# PCB.net
KiCad netlist of a schematic drawn in EAGLE
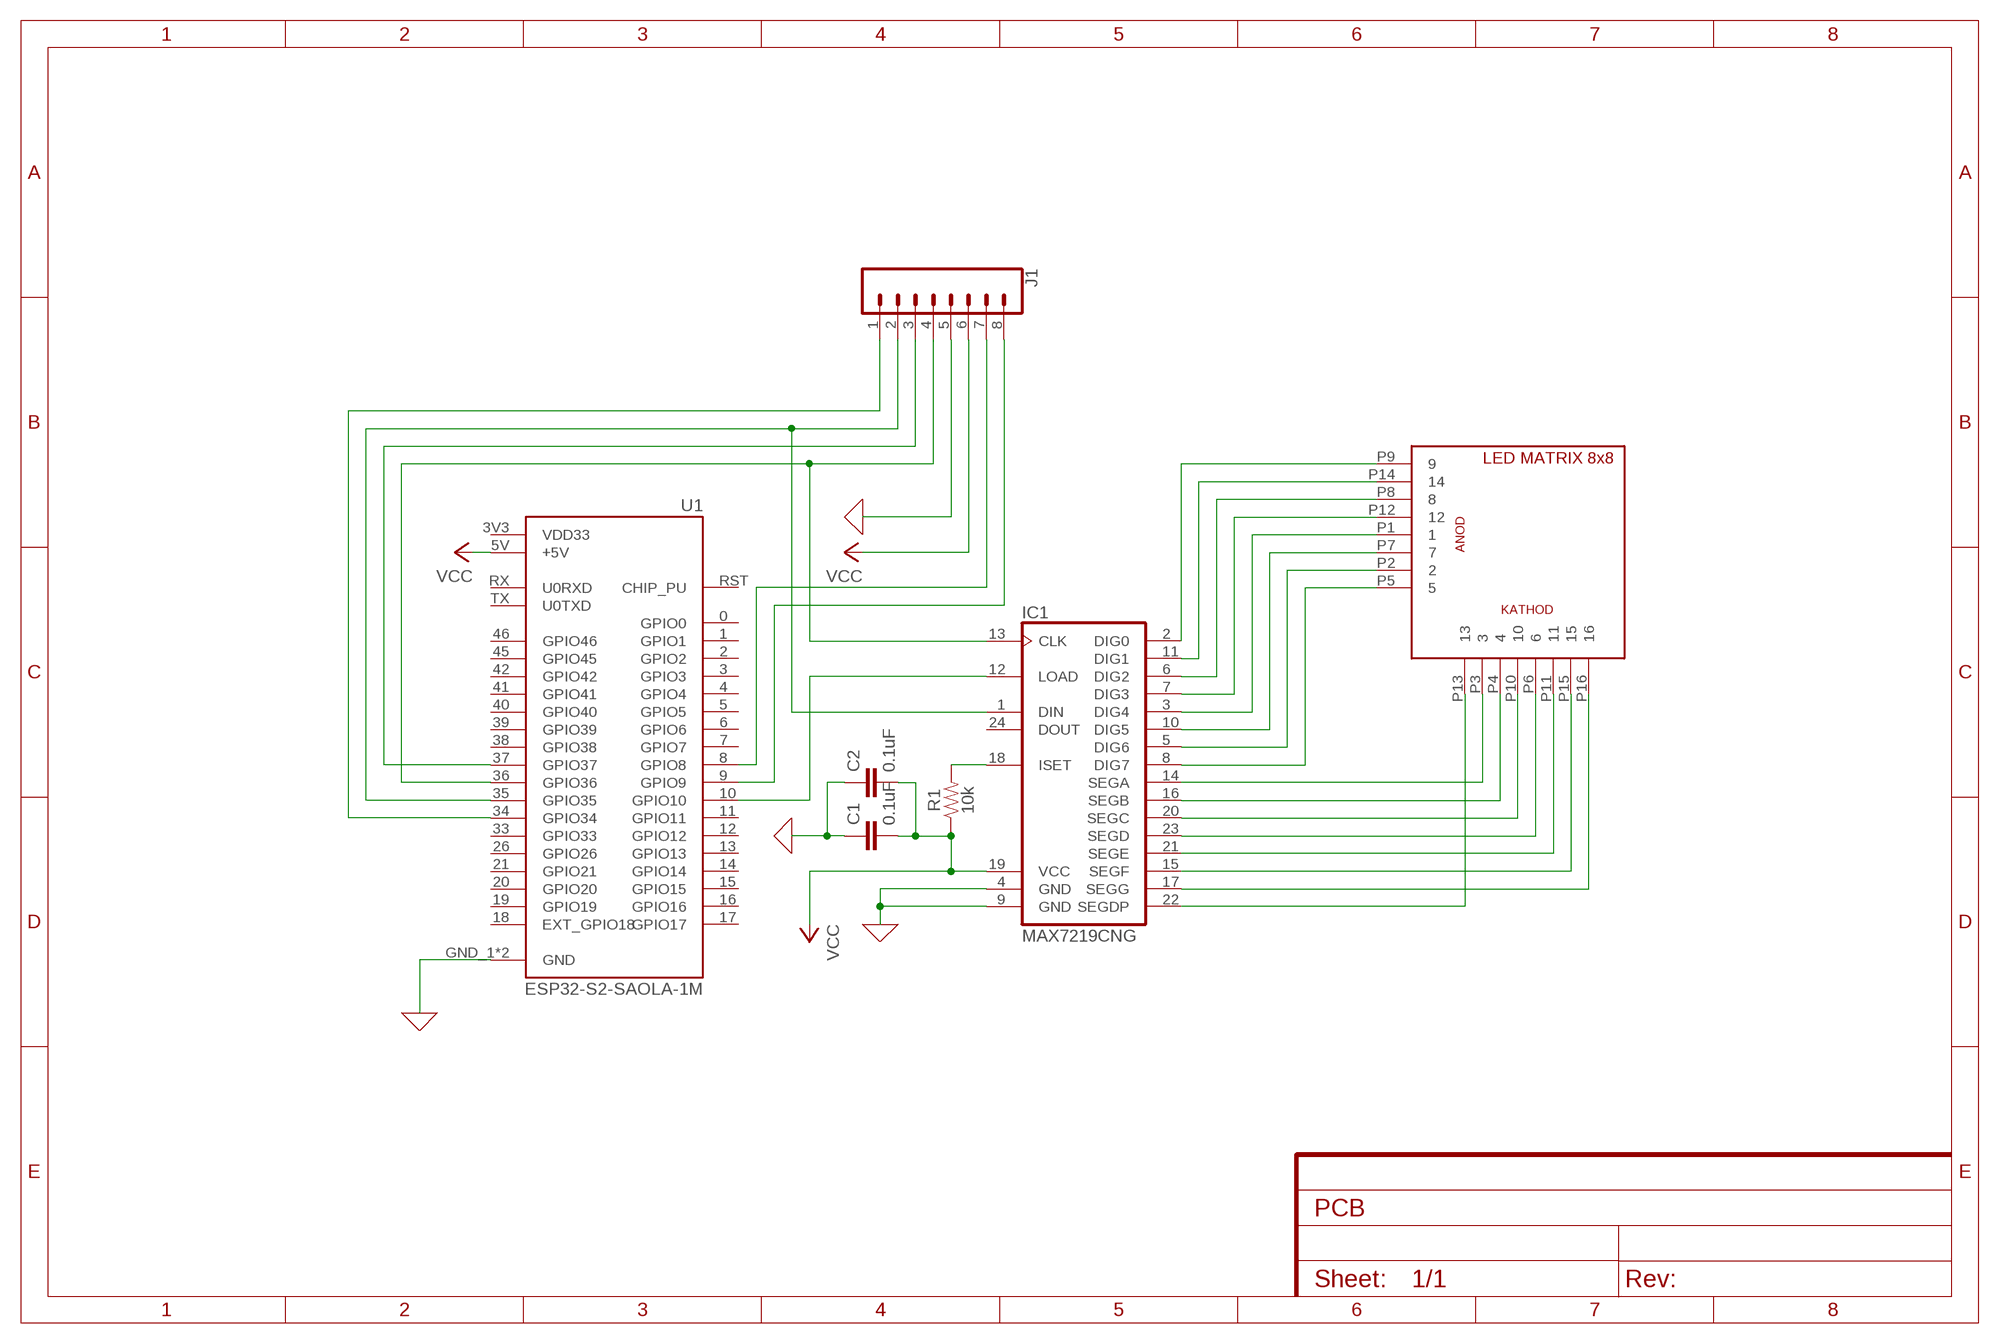
[diagram p0: schematic, sheet 1]

(export (version "E")
  (design (tool "Eeschema 10.0.6"))
  (components
    (comp (ref "C1")
      (value "0.1uF")
      (footprint "eagle-import:CAP-PTH-SMALL-KIT")
      (libsource (lib "eagle-import") (part "0.1UF-KIT-EZ-50V-20%"))
    )
    (comp (ref "C2")
      (value "0.1uF")
      (footprint "eagle-import:CAP-PTH-SMALL-KIT")
      (libsource (lib "eagle-import") (part "0.1UF-KIT-EZ-50V-20%"))
    )
    (comp (ref "IC1")
      (value "MAX7219CNG")
      (footprint "eagle-import:DIL24-3")
      (fields (field (name "MF") "MAXIM"))
      (libsource (lib "eagle-import") (part "MAX7219CNG"))
    )
    (comp (ref "J1")
      (value "CONN_08\"")
      (footprint "eagle-import:1X08")
      (libsource (lib "eagle-import") (part "CONN_08{dblquote}"))
    )
    (comp (ref "R1")
      (value "10k")
      (footprint "eagle-import:AXIAL-0.3")
      (libsource (lib "eagle-import") (part "10KOHM-HORIZ-1/4W-1%"))
    )
    (comp (ref "U$2")
      (value "LEDMAT8X8THROUGH_HOLE")
      (footprint "eagle-import:LEDMAT8X8")
      (libsource (lib "eagle-import") (part "LEDMAT8X8THROUGH_HOLE"))
    )
    (comp (ref "U1")
      (value "ESP32-S2-SAOLA-1M")
      (footprint "eagle-import:MODULE_ESP32-S2-SAOLA-1M")
      (fields (field (name "MF") "Espressif Systems"))
      (libsource (lib "eagle-import") (part "ESP32-S2-SAOLA-1M"))
    )
  )
  (nets
    (net (code "1") (name "/VDD33") (class "Default")
      (node (ref "U1") (pin "3V3") (pinfunction "VDD33_3V3") (pintype "power_in"))
    )
    (net (code "2") (name "GND") (class "Default")
      (node (ref "C1") (pin "1") (pinfunction "1_1") (pintype "passive"))
      (node (ref "C2") (pin "1") (pinfunction "1_1") (pintype "passive"))
      (node (ref "IC1") (pin "4") (pinfunction "GND_4") (pintype "power_in"))
      (node (ref "IC1") (pin "9") (pinfunction "GND_9") (pintype "power_in"))
      (node (ref "J1") (pin "5") (pinfunction "5_5") (pintype "passive"))
      (node (ref "U1") (pin "GND_1") (pinfunction "GND_GND_1") (pintype "power_in"))
      (node (ref "U1") (pin "GND_2") (pinfunction "GND_GND_2") (pintype "power_in"))
    )
    (net (code "3") (name "Net-(IC1-CLK)") (class "Default")
      (node (ref "IC1") (pin "13") (pinfunction "CLK_13") (pintype "input"))
      (node (ref "J1") (pin "4") (pinfunction "4_4") (pintype "passive"))
      (node (ref "U1") (pin "36") (pinfunction "GPIO36_36") (pintype "bidirectional"))
    )
    (net (code "4") (name "Net-(IC1-DIG0)") (class "Default")
      (node (ref "IC1") (pin "2") (pinfunction "DIG0_2") (pintype "output"))
      (node (ref "U$2") (pin "P9") (pinfunction "9_P9") (pintype "bidirectional"))
    )
    (net (code "5") (name "Net-(IC1-DIG1)") (class "Default")
      (node (ref "IC1") (pin "11") (pinfunction "DIG1_11") (pintype "output"))
      (node (ref "U$2") (pin "P14") (pinfunction "14_P14") (pintype "bidirectional"))
    )
    (net (code "6") (name "Net-(IC1-DIG2)") (class "Default")
      (node (ref "IC1") (pin "6") (pinfunction "DIG2_6") (pintype "output"))
      (node (ref "U$2") (pin "P8") (pinfunction "8_P8") (pintype "bidirectional"))
    )
    (net (code "7") (name "Net-(IC1-DIG3)") (class "Default")
      (node (ref "IC1") (pin "7") (pinfunction "DIG3_7") (pintype "output"))
      (node (ref "U$2") (pin "P12") (pinfunction "12_P12") (pintype "bidirectional"))
    )
    (net (code "8") (name "Net-(IC1-DIG4)") (class "Default")
      (node (ref "IC1") (pin "3") (pinfunction "DIG4_3") (pintype "output"))
      (node (ref "U$2") (pin "P1") (pinfunction "1_P1") (pintype "bidirectional"))
    )
    (net (code "9") (name "Net-(IC1-DIG5)") (class "Default")
      (node (ref "IC1") (pin "10") (pinfunction "DIG5_10") (pintype "output"))
      (node (ref "U$2") (pin "P7") (pinfunction "7_P7") (pintype "bidirectional"))
    )
    (net (code "10") (name "Net-(IC1-DIG6)") (class "Default")
      (node (ref "IC1") (pin "5") (pinfunction "DIG6_5") (pintype "output"))
      (node (ref "U$2") (pin "P2") (pinfunction "2_P2") (pintype "bidirectional"))
    )
    (net (code "11") (name "Net-(IC1-DIG7)") (class "Default")
      (node (ref "IC1") (pin "8") (pinfunction "DIG7_8") (pintype "output"))
      (node (ref "U$2") (pin "P5") (pinfunction "5_P5") (pintype "bidirectional"))
    )
    (net (code "12") (name "Net-(IC1-DIN)") (class "Default")
      (node (ref "IC1") (pin "1") (pinfunction "DIN_1") (pintype "input"))
      (node (ref "J1") (pin "2") (pinfunction "2_2") (pintype "passive"))
      (node (ref "U1") (pin "35") (pinfunction "GPIO35_35") (pintype "bidirectional"))
    )
    (net (code "13") (name "Net-(IC1-ISET)") (class "Default")
      (node (ref "IC1") (pin "18") (pinfunction "ISET_18") (pintype "input"))
      (node (ref "R1") (pin "P$2") (pinfunction "2_P$2") (pintype "passive"))
    )
    (net (code "14") (name "Net-(IC1-LOAD)") (class "Default")
      (node (ref "IC1") (pin "12") (pinfunction "LOAD_12") (pintype "input"))
      (node (ref "U1") (pin "10") (pinfunction "GPIO10_10") (pintype "bidirectional"))
    )
    (net (code "15") (name "Net-(IC1-SEGA)") (class "Default")
      (node (ref "IC1") (pin "14") (pinfunction "SEGA_14") (pintype "output"))
      (node (ref "U$2") (pin "P3") (pinfunction "3_P3") (pintype "bidirectional"))
    )
    (net (code "16") (name "Net-(IC1-SEGB)") (class "Default")
      (node (ref "IC1") (pin "16") (pinfunction "SEGB_16") (pintype "output"))
      (node (ref "U$2") (pin "P4") (pinfunction "4_P4") (pintype "bidirectional"))
    )
    (net (code "17") (name "Net-(IC1-SEGC)") (class "Default")
      (node (ref "IC1") (pin "20") (pinfunction "SEGC_20") (pintype "output"))
      (node (ref "U$2") (pin "P10") (pinfunction "10_P10") (pintype "bidirectional"))
    )
    (net (code "18") (name "Net-(IC1-SEGD)") (class "Default")
      (node (ref "IC1") (pin "23") (pinfunction "SEGD_23") (pintype "output"))
      (node (ref "U$2") (pin "P6") (pinfunction "6_P6") (pintype "bidirectional"))
    )
    (net (code "19") (name "Net-(IC1-SEGDP)") (class "Default")
      (node (ref "IC1") (pin "22") (pinfunction "SEGDP_22") (pintype "output"))
      (node (ref "U$2") (pin "P13") (pinfunction "13_P13") (pintype "bidirectional"))
    )
    (net (code "20") (name "Net-(IC1-SEGE)") (class "Default")
      (node (ref "IC1") (pin "21") (pinfunction "SEGE_21") (pintype "output"))
      (node (ref "U$2") (pin "P11") (pinfunction "11_P11") (pintype "bidirectional"))
    )
    (net (code "21") (name "Net-(IC1-SEGF)") (class "Default")
      (node (ref "IC1") (pin "15") (pinfunction "SEGF_15") (pintype "output"))
      (node (ref "U$2") (pin "P15") (pinfunction "15_P15") (pintype "bidirectional"))
    )
    (net (code "22") (name "Net-(IC1-SEGG)") (class "Default")
      (node (ref "IC1") (pin "17") (pinfunction "SEGG_17") (pintype "output"))
      (node (ref "U$2") (pin "P16") (pinfunction "16_P16") (pintype "bidirectional"))
    )
    (net (code "23") (name "Net-(U1-GPIO8)") (class "Default")
      (node (ref "J1") (pin "7") (pinfunction "7_7") (pintype "passive"))
      (node (ref "U1") (pin "8") (pinfunction "GPIO8_8") (pintype "bidirectional"))
    )
    (net (code "24") (name "Net-(U1-GPIO9)") (class "Default")
      (node (ref "J1") (pin "8") (pinfunction "8_8") (pintype "passive"))
      (node (ref "U1") (pin "9") (pinfunction "GPIO9_9") (pintype "bidirectional"))
    )
    (net (code "25") (name "Net-(U1-GPIO34)") (class "Default")
      (node (ref "J1") (pin "1") (pinfunction "1_1") (pintype "passive"))
      (node (ref "U1") (pin "34") (pinfunction "GPIO34_34") (pintype "bidirectional"))
    )
    (net (code "26") (name "Net-(U1-GPIO37)") (class "Default")
      (node (ref "J1") (pin "3") (pinfunction "3_3") (pintype "passive"))
      (node (ref "U1") (pin "37") (pinfunction "GPIO37_37") (pintype "bidirectional"))
    )
    (net (code "27") (name "VCC") (class "Default")
      (node (ref "C1") (pin "2") (pinfunction "2_2") (pintype "passive"))
      (node (ref "C2") (pin "2") (pinfunction "2_2") (pintype "passive"))
      (node (ref "IC1") (pin "19") (pinfunction "VCC_19") (pintype "power_in"))
      (node (ref "J1") (pin "6") (pinfunction "6_6") (pintype "passive"))
      (node (ref "R1") (pin "P$1") (pinfunction "1_P$1") (pintype "passive"))
      (node (ref "U1") (pin "5V") (pinfunction "+5V_5V") (pintype "power_in"))
    )
    (net (code "28") (name "unconnected-(IC1-DOUT-Pad24)") (class "Default")
      (node (ref "IC1") (pin "24") (pinfunction "DOUT_24") (pintype "output"))
    )
    (net (code "29") (name "unconnected-(U1-CHIP_PU-PadRST)") (class "Default")
      (node (ref "U1") (pin "RST") (pinfunction "CHIP_PU_RST") (pintype "bidirectional"))
    )
    (net (code "30") (name "unconnected-(U1-EXT_GPIO18-Pad18)") (class "Default")
      (node (ref "U1") (pin "18") (pinfunction "EXT_GPIO18_18") (pintype "bidirectional"))
    )
    (net (code "31") (name "unconnected-(U1-GPIO0-Pad0)") (class "Default")
      (node (ref "U1") (pin "0") (pinfunction "GPIO0_0") (pintype "bidirectional"))
    )
    (net (code "32") (name "unconnected-(U1-GPIO1-Pad1)") (class "Default")
      (node (ref "U1") (pin "1") (pinfunction "GPIO1_1") (pintype "bidirectional"))
    )
    (net (code "33") (name "unconnected-(U1-GPIO2-Pad2)") (class "Default")
      (node (ref "U1") (pin "2") (pinfunction "GPIO2_2") (pintype "bidirectional"))
    )
    (net (code "34") (name "unconnected-(U1-GPIO3-Pad3)") (class "Default")
      (node (ref "U1") (pin "3") (pinfunction "GPIO3_3") (pintype "bidirectional"))
    )
    (net (code "35") (name "unconnected-(U1-GPIO4-Pad4)") (class "Default")
      (node (ref "U1") (pin "4") (pinfunction "GPIO4_4") (pintype "bidirectional"))
    )
    (net (code "36") (name "unconnected-(U1-GPIO5-Pad5)") (class "Default")
      (node (ref "U1") (pin "5") (pinfunction "GPIO5_5") (pintype "bidirectional"))
    )
    (net (code "37") (name "unconnected-(U1-GPIO6-Pad6)") (class "Default")
      (node (ref "U1") (pin "6") (pinfunction "GPIO6_6") (pintype "bidirectional"))
    )
    (net (code "38") (name "unconnected-(U1-GPIO7-Pad7)") (class "Default")
      (node (ref "U1") (pin "7") (pinfunction "GPIO7_7") (pintype "bidirectional"))
    )
    (net (code "39") (name "unconnected-(U1-GPIO11-Pad11)") (class "Default")
      (node (ref "U1") (pin "11") (pinfunction "GPIO11_11") (pintype "bidirectional"))
    )
    (net (code "40") (name "unconnected-(U1-GPIO12-Pad12)") (class "Default")
      (node (ref "U1") (pin "12") (pinfunction "GPIO12_12") (pintype "bidirectional"))
    )
    (net (code "41") (name "unconnected-(U1-GPIO13-Pad13)") (class "Default")
      (node (ref "U1") (pin "13") (pinfunction "GPIO13_13") (pintype "bidirectional"))
    )
    (net (code "42") (name "unconnected-(U1-GPIO14-Pad14)") (class "Default")
      (node (ref "U1") (pin "14") (pinfunction "GPIO14_14") (pintype "bidirectional"))
    )
    (net (code "43") (name "unconnected-(U1-GPIO15-Pad15)") (class "Default")
      (node (ref "U1") (pin "15") (pinfunction "GPIO15_15") (pintype "bidirectional"))
    )
    (net (code "44") (name "unconnected-(U1-GPIO16-Pad16)") (class "Default")
      (node (ref "U1") (pin "16") (pinfunction "GPIO16_16") (pintype "bidirectional"))
    )
    (net (code "45") (name "unconnected-(U1-GPIO17-Pad17)") (class "Default")
      (node (ref "U1") (pin "17") (pinfunction "GPIO17_17") (pintype "bidirectional"))
    )
    (net (code "46") (name "unconnected-(U1-GPIO19-Pad19)") (class "Default")
      (node (ref "U1") (pin "19") (pinfunction "GPIO19_19") (pintype "bidirectional"))
    )
    (net (code "47") (name "unconnected-(U1-GPIO20-Pad20)") (class "Default")
      (node (ref "U1") (pin "20") (pinfunction "GPIO20_20") (pintype "bidirectional"))
    )
    (net (code "48") (name "unconnected-(U1-GPIO21-Pad21)") (class "Default")
      (node (ref "U1") (pin "21") (pinfunction "GPIO21_21") (pintype "bidirectional"))
    )
    (net (code "49") (name "unconnected-(U1-GPIO26-Pad26)") (class "Default")
      (node (ref "U1") (pin "26") (pinfunction "GPIO26_26") (pintype "bidirectional"))
    )
    (net (code "50") (name "unconnected-(U1-GPIO33-Pad33)") (class "Default")
      (node (ref "U1") (pin "33") (pinfunction "GPIO33_33") (pintype "bidirectional"))
    )
    (net (code "51") (name "unconnected-(U1-GPIO38-Pad38)") (class "Default")
      (node (ref "U1") (pin "38") (pinfunction "GPIO38_38") (pintype "bidirectional"))
    )
    (net (code "52") (name "unconnected-(U1-GPIO39-Pad39)") (class "Default")
      (node (ref "U1") (pin "39") (pinfunction "GPIO39_39") (pintype "bidirectional"))
    )
    (net (code "53") (name "unconnected-(U1-GPIO40-Pad40)") (class "Default")
      (node (ref "U1") (pin "40") (pinfunction "GPIO40_40") (pintype "bidirectional"))
    )
    (net (code "54") (name "unconnected-(U1-GPIO41-Pad41)") (class "Default")
      (node (ref "U1") (pin "41") (pinfunction "GPIO41_41") (pintype "bidirectional"))
    )
    (net (code "55") (name "unconnected-(U1-GPIO42-Pad42)") (class "Default")
      (node (ref "U1") (pin "42") (pinfunction "GPIO42_42") (pintype "bidirectional"))
    )
    (net (code "56") (name "unconnected-(U1-GPIO45-Pad45)") (class "Default")
      (node (ref "U1") (pin "45") (pinfunction "GPIO45_45") (pintype "bidirectional"))
    )
    (net (code "57") (name "unconnected-(U1-GPIO46-Pad46)") (class "Default")
      (node (ref "U1") (pin "46") (pinfunction "GPIO46_46") (pintype "bidirectional"))
    )
    (net (code "58") (name "unconnected-(U1-U0RXD-PadRX)") (class "Default")
      (node (ref "U1") (pin "RX") (pinfunction "U0RXD_RX") (pintype "bidirectional"))
    )
    (net (code "59") (name "unconnected-(U1-U0TXD-PadTX)") (class "Default")
      (node (ref "U1") (pin "TX") (pinfunction "U0TXD_TX") (pintype "bidirectional"))
    )
  )
)
